# Mechanical.net
KiCad netlist of a schematic drawn in Altium Designer
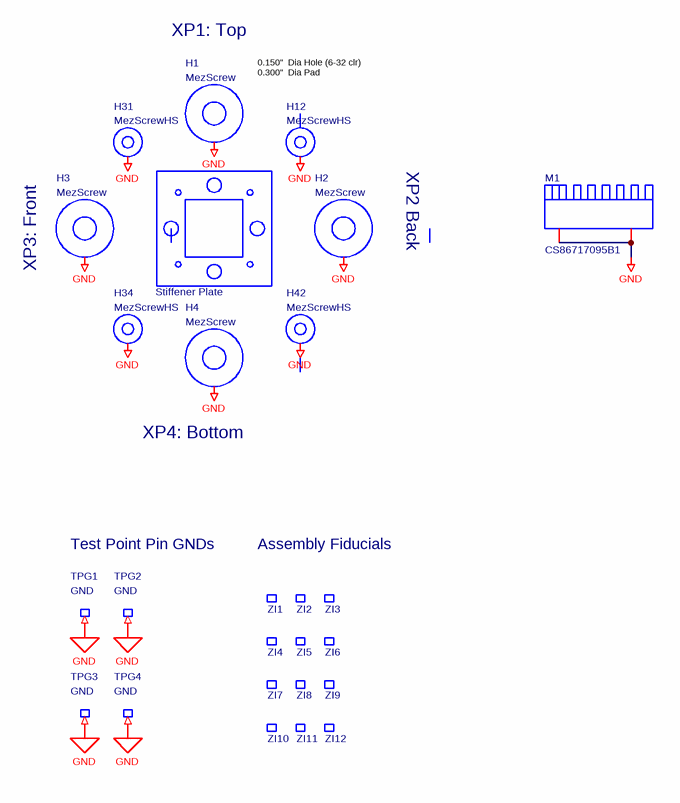
[diagram p0: Mechanical.SchDoc]

(export (version "E")
  (design (tool "Eeschema 10.0.6"))
  (components
    (comp (ref "H1")
      (value "MezScrew")
      (footprint "MC_S6/TH/SCREW_BASE")
      (libsource (lib "ALCT_MEZ_SPARTAN6_Library") (part "MezScrew"))
    )
    (comp (ref "H2")
      (value "MezScrew")
      (footprint "MC_S6/TH/SCREW_BASE")
      (libsource (lib "ALCT_MEZ_SPARTAN6_Library") (part "MezScrew"))
    )
    (comp (ref "H3")
      (value "MezScrew")
      (footprint "MC_S6/TH/SCREW_BASE")
      (libsource (lib "ALCT_MEZ_SPARTAN6_Library") (part "MezScrew"))
    )
    (comp (ref "H4")
      (value "MezScrew")
      (footprint "MC_S6/TH/SCREW_BASE")
      (libsource (lib "ALCT_MEZ_SPARTAN6_Library") (part "MezScrew"))
    )
    (comp (ref "H12")
      (value "MezScrewHS")
      (footprint "MC_S6/TH/SCREW_PLATE")
      (libsource (lib "ALCT_MEZ_SPARTAN6_Library") (part "MezScrewHS"))
    )
    (comp (ref "H31")
      (value "MezScrewHS")
      (footprint "MC_S6/TH/SCREW_PLATE")
      (libsource (lib "ALCT_MEZ_SPARTAN6_Library") (part "MezScrewHS"))
    )
    (comp (ref "H34")
      (value "MezScrewHS")
      (footprint "MC_S6/TH/SCREW_PLATE")
      (libsource (lib "ALCT_MEZ_SPARTAN6_Library") (part "MezScrewHS"))
    )
    (comp (ref "H42")
      (value "MezScrewHS")
      (footprint "MC_S6/TH/SCREW_PLATE")
      (libsource (lib "ALCT_MEZ_SPARTAN6_Library") (part "MezScrewHS"))
    )
    (comp (ref "M1")
      (value "CS86717095B1")
      (footprint "CS86717095B1")
      (description "Heatsink 17 x 17 x 9.5mm")
      (libsource (lib "ALCT_MEZ_SPARTAN6_Library") (part "CS86717095B1"))
    )
    (comp (ref "SP1")
      (value "Stiffener Plate")
      (footprint "MC_S6/SPLATE")
      (libsource (lib "ALCT_MEZ_SPARTAN6_Library") (part "SPlate_MC_S6"))
    )
    (comp (ref "TPG1") (value "GND") (footprint "MC_S6/TH/TPGND") (libsource (lib "*") (part "TPGND")))
    (comp (ref "TPG2") (value "GND") (footprint "MC_S6/TH/TPGND") (libsource (lib "*") (part "TPGND")))
    (comp (ref "TPG3") (value "GND") (footprint "MC_S6/TH/TPGND") (libsource (lib "*") (part "TPGND")))
    (comp (ref "TPG4") (value "GND") (footprint "MC_S6/TH/TPGND") (libsource (lib "*") (part "TPGND")))
    (comp (ref "ZI1")
      (value "Fiducial Dot")
      (footprint "MC_S6/SM/FIDUCIAL_DOT")
      (libsource (lib "ALCT_MEZ_SPARTAN6_Library") (part "Fiducial_dot"))
    )
    (comp (ref "ZI2")
      (value "Fiducial Dot")
      (footprint "MC_S6/SM/FIDUCIAL_DOT")
      (libsource (lib "ALCT_MEZ_SPARTAN6_Library") (part "Fiducial_dot"))
    )
    (comp (ref "ZI3")
      (value "Fiducial Dot")
      (footprint "MC_S6/SM/FIDUCIAL_DOT")
      (libsource (lib "ALCT_MEZ_SPARTAN6_Library") (part "Fiducial_dot"))
    )
    (comp (ref "ZI4")
      (value "Fiducial Dot")
      (footprint "MC_S6/SM/FIDUCIAL_DOT")
      (libsource (lib "ALCT_MEZ_SPARTAN6_Library") (part "Fiducial_dot"))
    )
    (comp (ref "ZI5")
      (value "Fiducial Dot")
      (footprint "MC_S6/SM/FIDUCIAL_DOT")
      (libsource (lib "ALCT_MEZ_SPARTAN6_Library") (part "Fiducial_dot"))
    )
    (comp (ref "ZI6")
      (value "Fiducial Dot")
      (footprint "MC_S6/SM/FIDUCIAL_DOT")
      (libsource (lib "ALCT_MEZ_SPARTAN6_Library") (part "Fiducial_dot"))
    )
    (comp (ref "ZI7")
      (value "Fiducial Dot")
      (footprint "MC_S6/SM/FIDUCIAL_DOT")
      (libsource (lib "ALCT_MEZ_SPARTAN6_Library") (part "Fiducial_dot"))
    )
    (comp (ref "ZI8")
      (value "Fiducial Dot")
      (footprint "MC_S6/SM/FIDUCIAL_DOT")
      (libsource (lib "ALCT_MEZ_SPARTAN6_Library") (part "Fiducial_dot"))
    )
    (comp (ref "ZI9")
      (value "Fiducial Dot")
      (footprint "MC_S6/SM/FIDUCIAL_DOT")
      (libsource (lib "ALCT_MEZ_SPARTAN6_Library") (part "Fiducial_dot"))
    )
    (comp (ref "ZI10")
      (value "Fiducial Dot")
      (footprint "MC_S6/SM/FIDUCIAL_DOT")
      (libsource (lib "ALCT_MEZ_SPARTAN6_Library") (part "Fiducial_dot"))
    )
    (comp (ref "ZI11")
      (value "Fiducial Dot")
      (footprint "MC_S6/SM/FIDUCIAL_DOT")
      (libsource (lib "ALCT_MEZ_SPARTAN6_Library") (part "Fiducial_dot"))
    )
    (comp (ref "ZI12")
      (value "Fiducial Dot")
      (footprint "MC_S6/SM/FIDUCIAL_DOT")
      (libsource (lib "ALCT_MEZ_SPARTAN6_Library") (part "Fiducial_dot"))
    )
  )
  (nets
    (net (code "1") (name "GND") (class "Default")
      (node (ref "H1") (pin "1") (pinfunction "GND_1") (pintype "power_in"))
      (node (ref "H12") (pin "1") (pinfunction "GND_1") (pintype "power_in"))
      (node (ref "H2") (pin "1") (pinfunction "GND_1") (pintype "power_in"))
      (node (ref "H3") (pin "1") (pinfunction "GND_1") (pintype "power_in"))
      (node (ref "H31") (pin "1") (pinfunction "GND_1") (pintype "power_in"))
      (node (ref "H34") (pin "1") (pinfunction "GND_1") (pintype "power_in"))
      (node (ref "H4") (pin "1") (pinfunction "GND_1") (pintype "power_in"))
      (node (ref "H42") (pin "1") (pinfunction "GND_1") (pintype "power_in"))
      (node (ref "M1") (pin "1") (pinfunction "1_1") (pintype "passive"))
      (node (ref "M1") (pin "2") (pinfunction "4_2") (pintype "passive"))
      (node (ref "TPG1") (pin "1") (pinfunction "In_1") (pintype "input"))
      (node (ref "TPG2") (pin "1") (pinfunction "In_1") (pintype "input"))
      (node (ref "TPG3") (pin "1") (pinfunction "In_1") (pintype "input"))
      (node (ref "TPG4") (pin "1") (pinfunction "In_1") (pintype "input"))
    )
    (net (code "2") (name "unconnected-(ZI1-NC-Pad1)") (class "Default")
      (node (ref "ZI1") (pin "1") (pinfunction "NC_1") (pintype "passive"))
    )
    (net (code "3") (name "unconnected-(ZI2-NC-Pad1)") (class "Default")
      (node (ref "ZI2") (pin "1") (pinfunction "NC_1") (pintype "passive"))
    )
    (net (code "4") (name "unconnected-(ZI3-NC-Pad1)") (class "Default")
      (node (ref "ZI3") (pin "1") (pinfunction "NC_1") (pintype "passive"))
    )
    (net (code "5") (name "unconnected-(ZI4-NC-Pad1)") (class "Default")
      (node (ref "ZI4") (pin "1") (pinfunction "NC_1") (pintype "passive"))
    )
    (net (code "6") (name "unconnected-(ZI5-NC-Pad1)") (class "Default")
      (node (ref "ZI5") (pin "1") (pinfunction "NC_1") (pintype "passive"))
    )
    (net (code "7") (name "unconnected-(ZI6-NC-Pad1)") (class "Default")
      (node (ref "ZI6") (pin "1") (pinfunction "NC_1") (pintype "passive"))
    )
    (net (code "8") (name "unconnected-(ZI7-NC-Pad1)") (class "Default")
      (node (ref "ZI7") (pin "1") (pinfunction "NC_1") (pintype "passive"))
    )
    (net (code "9") (name "unconnected-(ZI8-NC-Pad1)") (class "Default")
      (node (ref "ZI8") (pin "1") (pinfunction "NC_1") (pintype "passive"))
    )
    (net (code "10") (name "unconnected-(ZI9-NC-Pad1)") (class "Default")
      (node (ref "ZI9") (pin "1") (pinfunction "NC_1") (pintype "passive"))
    )
    (net (code "11") (name "unconnected-(ZI10-NC-Pad1)") (class "Default")
      (node (ref "ZI10") (pin "1") (pinfunction "NC_1") (pintype "passive"))
    )
    (net (code "12") (name "unconnected-(ZI11-NC-Pad1)") (class "Default")
      (node (ref "ZI11") (pin "1") (pinfunction "NC_1") (pintype "passive"))
    )
    (net (code "13") (name "unconnected-(ZI12-NC-Pad1)") (class "Default")
      (node (ref "ZI12") (pin "1") (pinfunction "NC_1") (pintype "passive"))
    )
  )
)
